# DDR-LPDDR4.net
KiCad netlist of a schematic drawn in Altium Designer
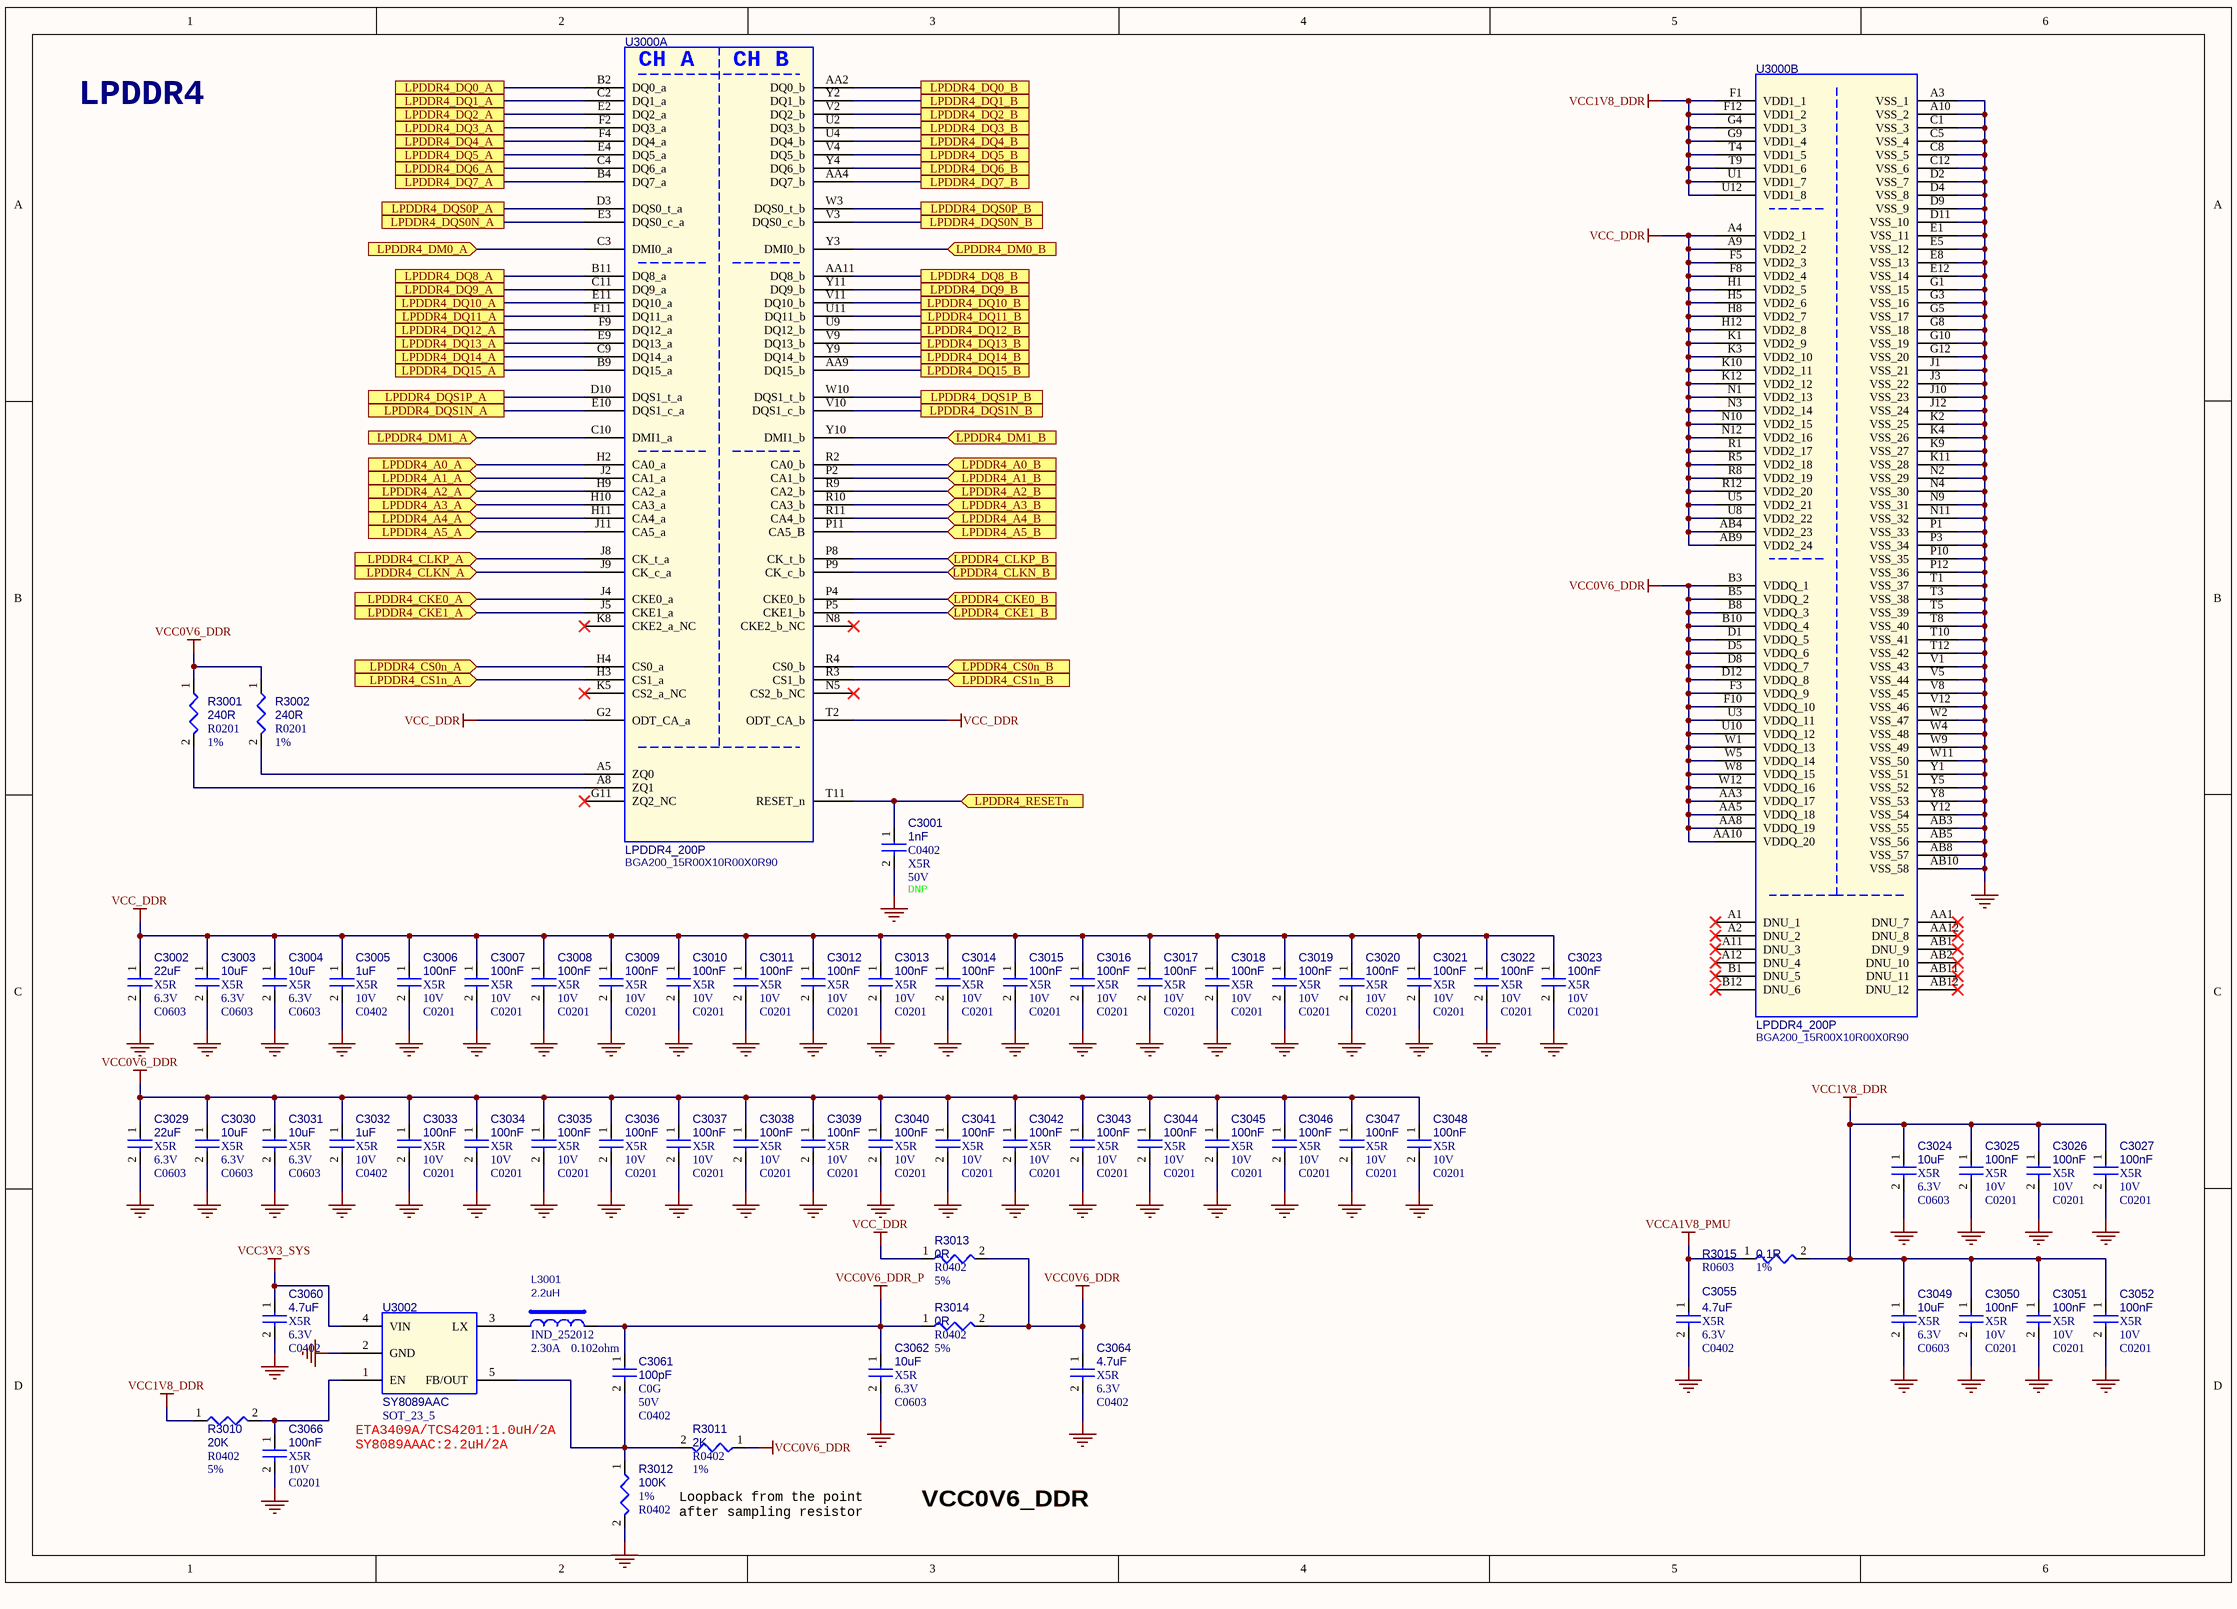
[diagram p0: DDR-LPDDR4.SchDoc]

(export (version "E")
  (design (tool "Eeschema 10.0.6"))
  (components
    (comp (ref "C3001")
      (value "1nF")
      (footprint "C0402")
      (description "cap,1.00nF,+/-10%,50V,X5R,C0402")
      (fields
        (field (name "DIELECTRIC") "X5R")
        (field (name "PCB FOOTPRINT") "C0402")
        (field (name "VOLTAGE") "50V")
        (field (name "OPTION") "DNP")
        (field (name "TOLERANCE") "10%")
        (field (name "MANUFACTURER") "TDK")
        (field (name "CREATED BY") "JJJ")
      )
      (libsource (lib "RK3562_REF") (part "CAP NP"))
    )
    (comp (ref "C3002")
      (value "22uF")
      (footprint "C0603")
      (description "cap,22.00uF,+/-20%,6.3V,X5R,C0603")
      (fields
        (field (name "DIELECTRIC") "X5R")
        (field (name "PCB FOOTPRINT") "C0603")
        (field (name "VOLTAGE") "6.3V")
        (field (name "MANUFACTURER") "TDK")
        (field (name "TOLERANCE") "20%")
        (field (name "CREATED BY") "JJJ")
      )
      (libsource (lib "RK3562_REF") (part "CAP NP"))
    )
    (comp (ref "C3003")
      (value "10uF")
      (footprint "C0603")
      (description "cap,10.00uF,+/-10%,6.3V,X5R,C0603")
      (fields
        (field (name "DIELECTRIC") "X5R")
        (field (name "PCB FOOTPRINT") "C0603")
        (field (name "VOLTAGE") "6.3V")
        (field (name "MANUFACTURER") "TDK")
        (field (name "TOLERANCE") "10%")
        (field (name "CREATED BY") "JJJ")
      )
      (libsource (lib "RK3562_REF") (part "CAP NP"))
    )
    (comp (ref "C3004")
      (value "10uF")
      (footprint "C0603")
      (description "cap,10.00uF,+/-10%,6.3V,X5R,C0603")
      (fields
        (field (name "DIELECTRIC") "X5R")
        (field (name "PCB FOOTPRINT") "C0603")
        (field (name "VOLTAGE") "6.3V")
        (field (name "TOLERANCE") "10%")
        (field (name "MANUFACTURER") "TDK")
        (field (name "CREATED BY") "JJJ")
      )
      (libsource (lib "RK3562_REF") (part "CAP NP"))
    )
    (comp (ref "C3005")
      (value "1uF")
      (footprint "C0402")
      (description "cap,1.00uF,+/-10%,10V,X5R,C0402")
      (fields
        (field (name "DIELECTRIC") "X5R")
        (field (name "PCB FOOTPRINT") "C0402")
        (field (name "VOLTAGE") "10V")
        (field (name "MANUFACTURER") "TDK")
        (field (name "TOLERANCE") "10%")
        (field (name "CREATED BY") "JJJ")
      )
      (libsource (lib "RK3562_REF") (part "CAP NP"))
    )
    (comp (ref "C3006")
      (value "100nF")
      (footprint "C0201")
      (description "cap,100.00nF,+/-10%,10V,X5R,C0201")
      (fields
        (field (name "DIELECTRIC") "X5R")
        (field (name "PCB FOOTPRINT") "C0201")
        (field (name "VOLTAGE") "10V")
        (field (name "MANUFACTURER") "TDK")
        (field (name "TOLERANCE") "10%")
        (field (name "CREATED BY") "JJJ")
      )
      (libsource (lib "RK3562_REF") (part "CAP NP"))
    )
    (comp (ref "C3007")
      (value "100nF")
      (footprint "C0201")
      (description "cap,100.00nF,+/-10%,10V,X5R,C0201")
      (fields
        (field (name "DIELECTRIC") "X5R")
        (field (name "PCB FOOTPRINT") "C0201")
        (field (name "VOLTAGE") "10V")
        (field (name "MANUFACTURER") "TDK")
        (field (name "TOLERANCE") "10%")
        (field (name "CREATED BY") "JJJ")
      )
      (libsource (lib "RK3562_REF") (part "CAP NP"))
    )
    (comp (ref "C3008")
      (value "100nF")
      (footprint "C0201")
      (description "cap,100.00nF,+/-10%,10V,X5R,C0201")
      (fields
        (field (name "DIELECTRIC") "X5R")
        (field (name "PCB FOOTPRINT") "C0201")
        (field (name "VOLTAGE") "10V")
        (field (name "MANUFACTURER") "TDK")
        (field (name "TOLERANCE") "10%")
        (field (name "CREATED BY") "JJJ")
      )
      (libsource (lib "RK3562_REF") (part "CAP NP"))
    )
    (comp (ref "C3009")
      (value "100nF")
      (footprint "C0201")
      (description "cap,100.00nF,+/-10%,10V,X5R,C0201")
      (fields
        (field (name "DIELECTRIC") "X5R")
        (field (name "PCB FOOTPRINT") "C0201")
        (field (name "VOLTAGE") "10V")
        (field (name "MANUFACTURER") "TDK")
        (field (name "TOLERANCE") "10%")
        (field (name "CREATED BY") "JJJ")
      )
      (libsource (lib "RK3562_REF") (part "CAP NP"))
    )
    (comp (ref "C3010")
      (value "100nF")
      (footprint "C0201")
      (description "cap,100.00nF,+/-10%,10V,X5R,C0201")
      (fields
        (field (name "DIELECTRIC") "X5R")
        (field (name "PCB FOOTPRINT") "C0201")
        (field (name "VOLTAGE") "10V")
        (field (name "MANUFACTURER") "TDK")
        (field (name "TOLERANCE") "10%")
        (field (name "CREATED BY") "JJJ")
      )
      (libsource (lib "RK3562_REF") (part "CAP NP"))
    )
    (comp (ref "C3011")
      (value "100nF")
      (footprint "C0201")
      (description "cap,100.00nF,+/-10%,10V,X5R,C0201")
      (fields
        (field (name "DIELECTRIC") "X5R")
        (field (name "PCB FOOTPRINT") "C0201")
        (field (name "VOLTAGE") "10V")
        (field (name "MANUFACTURER") "TDK")
        (field (name "TOLERANCE") "10%")
        (field (name "CREATED BY") "JJJ")
      )
      (libsource (lib "RK3562_REF") (part "CAP NP"))
    )
    (comp (ref "C3012")
      (value "100nF")
      (footprint "C0201")
      (description "cap,100.00nF,+/-10%,10V,X5R,C0201")
      (fields
        (field (name "DIELECTRIC") "X5R")
        (field (name "PCB FOOTPRINT") "C0201")
        (field (name "VOLTAGE") "10V")
        (field (name "TOLERANCE") "10%")
        (field (name "MANUFACTURER") "TDK")
        (field (name "CREATED BY") "JJJ")
      )
      (libsource (lib "RK3562_REF") (part "CAP NP"))
    )
    (comp (ref "C3013")
      (value "100nF")
      (footprint "C0201")
      (description "cap,100.00nF,+/-10%,10V,X5R,C0201")
      (fields
        (field (name "DIELECTRIC") "X5R")
        (field (name "PCB FOOTPRINT") "C0201")
        (field (name "VOLTAGE") "10V")
        (field (name "TOLERANCE") "10%")
        (field (name "MANUFACTURER") "TDK")
        (field (name "CREATED BY") "JJJ")
      )
      (libsource (lib "RK3562_REF") (part "CAP NP"))
    )
    (comp (ref "C3014")
      (value "100nF")
      (footprint "C0201")
      (description "cap,100.00nF,+/-10%,10V,X5R,C0201")
      (fields
        (field (name "DIELECTRIC") "X5R")
        (field (name "PCB FOOTPRINT") "C0201")
        (field (name "VOLTAGE") "10V")
        (field (name "TOLERANCE") "10%")
        (field (name "MANUFACTURER") "TDK")
        (field (name "CREATED BY") "JJJ")
      )
      (libsource (lib "RK3562_REF") (part "CAP NP"))
    )
    (comp (ref "C3015")
      (value "100nF")
      (footprint "C0201")
      (description "cap,100.00nF,+/-10%,10V,X5R,C0201")
      (fields
        (field (name "DIELECTRIC") "X5R")
        (field (name "PCB FOOTPRINT") "C0201")
        (field (name "VOLTAGE") "10V")
        (field (name "TOLERANCE") "10%")
        (field (name "MANUFACTURER") "TDK")
        (field (name "CREATED BY") "JJJ")
      )
      (libsource (lib "RK3562_REF") (part "CAP NP"))
    )
    (comp (ref "C3016")
      (value "100nF")
      (footprint "C0201")
      (description "cap,100.00nF,+/-10%,10V,X5R,C0201")
      (fields
        (field (name "DIELECTRIC") "X5R")
        (field (name "PCB FOOTPRINT") "C0201")
        (field (name "VOLTAGE") "10V")
        (field (name "TOLERANCE") "10%")
        (field (name "MANUFACTURER") "TDK")
        (field (name "CREATED BY") "JJJ")
      )
      (libsource (lib "RK3562_REF") (part "CAP NP"))
    )
    (comp (ref "C3017")
      (value "100nF")
      (footprint "C0201")
      (description "cap,100.00nF,+/-10%,10V,X5R,C0201")
      (fields
        (field (name "DIELECTRIC") "X5R")
        (field (name "PCB FOOTPRINT") "C0201")
        (field (name "VOLTAGE") "10V")
        (field (name "MANUFACTURER") "TDK")
        (field (name "TOLERANCE") "10%")
        (field (name "CREATED BY") "JJJ")
      )
      (libsource (lib "RK3562_REF") (part "CAP NP"))
    )
    (comp (ref "C3018")
      (value "100nF")
      (footprint "C0201")
      (description "cap,100.00nF,+/-10%,10V,X5R,C0201")
      (fields
        (field (name "DIELECTRIC") "X5R")
        (field (name "PCB FOOTPRINT") "C0201")
        (field (name "VOLTAGE") "10V")
        (field (name "MANUFACTURER") "TDK")
        (field (name "TOLERANCE") "10%")
        (field (name "CREATED BY") "JJJ")
      )
      (libsource (lib "RK3562_REF") (part "CAP NP"))
    )
    (comp (ref "C3019")
      (value "100nF")
      (footprint "C0201")
      (description "cap,100.00nF,+/-10%,10V,X5R,C0201")
      (fields
        (field (name "DIELECTRIC") "X5R")
        (field (name "PCB FOOTPRINT") "C0201")
        (field (name "VOLTAGE") "10V")
        (field (name "TOLERANCE") "10%")
        (field (name "MANUFACTURER") "TDK")
        (field (name "CREATED BY") "JJJ")
      )
      (libsource (lib "RK3562_REF") (part "CAP NP"))
    )
    (comp (ref "C3020")
      (value "100nF")
      (footprint "C0201")
      (description "cap,100.00nF,+/-10%,10V,X5R,C0201")
      (fields
        (field (name "DIELECTRIC") "X5R")
        (field (name "PCB FOOTPRINT") "C0201")
        (field (name "VOLTAGE") "10V")
        (field (name "TOLERANCE") "10%")
        (field (name "MANUFACTURER") "TDK")
        (field (name "CREATED BY") "JJJ")
      )
      (libsource (lib "RK3562_REF") (part "CAP NP"))
    )
    (comp (ref "C3021")
      (value "100nF")
      (footprint "C0201")
      (description "cap,100.00nF,+/-10%,10V,X5R,C0201")
      (fields
        (field (name "DIELECTRIC") "X5R")
        (field (name "PCB FOOTPRINT") "C0201")
        (field (name "VOLTAGE") "10V")
        (field (name "TOLERANCE") "10%")
        (field (name "MANUFACTURER") "TDK")
        (field (name "CREATED BY") "JJJ")
      )
      (libsource (lib "RK3562_REF") (part "CAP NP"))
    )
    (comp (ref "C3022")
      (value "100nF")
      (footprint "C0201")
      (description "cap,100.00nF,+/-10%,10V,X5R,C0201")
      (fields
        (field (name "DIELECTRIC") "X5R")
        (field (name "PCB FOOTPRINT") "C0201")
        (field (name "VOLTAGE") "10V")
        (field (name "MANUFACTURER") "TDK")
        (field (name "TOLERANCE") "10%")
        (field (name "CREATED BY") "JJJ")
      )
      (libsource (lib "RK3562_REF") (part "CAP NP"))
    )
    (comp (ref "C3023")
      (value "100nF")
      (footprint "C0201")
      (description "cap,100.00nF,+/-10%,10V,X5R,C0201")
      (fields
        (field (name "DIELECTRIC") "X5R")
        (field (name "PCB FOOTPRINT") "C0201")
        (field (name "VOLTAGE") "10V")
        (field (name "MANUFACTURER") "TDK")
        (field (name "TOLERANCE") "10%")
        (field (name "CREATED BY") "JJJ")
      )
      (libsource (lib "RK3562_REF") (part "CAP NP"))
    )
    (comp (ref "C3024")
      (value "10uF")
      (footprint "C0603")
      (description "cap,10.00uF,+/-10%,6.3V,X5R,C0603")
      (fields
        (field (name "DIELECTRIC") "X5R")
        (field (name "PCB FOOTPRINT") "C0603")
        (field (name "VOLTAGE") "6.3V")
        (field (name "TOLERANCE") "10%")
        (field (name "MANUFACTURER") "TDK")
        (field (name "CREATED BY") "JJJ")
      )
      (libsource (lib "RK3562_REF") (part "CAP NP"))
    )
    (comp (ref "C3025")
      (value "100nF")
      (footprint "C0201")
      (description "cap,100.00nF,+/-10%,10V,X5R,C0201")
      (fields
        (field (name "DIELECTRIC") "X5R")
        (field (name "PCB FOOTPRINT") "C0201")
        (field (name "VOLTAGE") "10V")
        (field (name "TOLERANCE") "10%")
        (field (name "MANUFACTURER") "TDK")
        (field (name "CREATED BY") "JJJ")
      )
      (libsource (lib "RK3562_REF") (part "CAP NP"))
    )
    (comp (ref "C3026")
      (value "100nF")
      (footprint "C0201")
      (description "cap,100.00nF,+/-10%,10V,X5R,C0201")
      (fields
        (field (name "DIELECTRIC") "X5R")
        (field (name "PCB FOOTPRINT") "C0201")
        (field (name "VOLTAGE") "10V")
        (field (name "TOLERANCE") "10%")
        (field (name "MANUFACTURER") "TDK")
        (field (name "CREATED BY") "JJJ")
      )
      (libsource (lib "RK3562_REF") (part "CAP NP"))
    )
    (comp (ref "C3027")
      (value "100nF")
      (footprint "C0201")
      (description "cap,100.00nF,+/-10%,10V,X5R,C0201")
      (fields
        (field (name "DIELECTRIC") "X5R")
        (field (name "PCB FOOTPRINT") "C0201")
        (field (name "VOLTAGE") "10V")
        (field (name "TOLERANCE") "10%")
        (field (name "MANUFACTURER") "TDK")
        (field (name "CREATED BY") "JJJ")
      )
      (libsource (lib "RK3562_REF") (part "CAP NP"))
    )
    (comp (ref "C3029")
      (value "22uF")
      (footprint "C0603")
      (description "cap,22.00uF,+/-20%,6.3V,X5R,C0603")
      (fields
        (field (name "DIELECTRIC") "X5R")
        (field (name "PCB FOOTPRINT") "C0603")
        (field (name "VOLTAGE") "6.3V")
        (field (name "TOLERANCE") "20%")
        (field (name "MANUFACTURER") "TDK")
        (field (name "CREATED BY") "JJJ")
      )
      (libsource (lib "RK3562_REF") (part "CAP NP"))
    )
    (comp (ref "C3030")
      (value "10uF")
      (footprint "C0603")
      (description "cap,10.00uF,+/-10%,6.3V,X5R,C0603")
      (fields
        (field (name "DIELECTRIC") "X5R")
        (field (name "PCB FOOTPRINT") "C0603")
        (field (name "VOLTAGE") "6.3V")
        (field (name "MANUFACTURER") "TDK")
        (field (name "TOLERANCE") "10%")
        (field (name "CREATED BY") "JJJ")
      )
      (libsource (lib "RK3562_REF") (part "CAP NP"))
    )
    (comp (ref "C3031")
      (value "10uF")
      (footprint "C0603")
      (description "cap,10.00uF,+/-10%,6.3V,X5R,C0603")
      (fields
        (field (name "DIELECTRIC") "X5R")
        (field (name "PCB FOOTPRINT") "C0603")
        (field (name "VOLTAGE") "6.3V")
        (field (name "TOLERANCE") "10%")
        (field (name "MANUFACTURER") "TDK")
        (field (name "CREATED BY") "JJJ")
      )
      (libsource (lib "RK3562_REF") (part "CAP NP"))
    )
    (comp (ref "C3032")
      (value "1uF")
      (footprint "C0402")
      (description "cap,1.00uF,+/-10%,10V,X5R,C0402")
      (fields
        (field (name "DIELECTRIC") "X5R")
        (field (name "PCB FOOTPRINT") "C0402")
        (field (name "VOLTAGE") "10V")
        (field (name "TOLERANCE") "10%")
        (field (name "MANUFACTURER") "TDK")
        (field (name "CREATED BY") "JJJ")
      )
      (libsource (lib "RK3562_REF") (part "CAP NP"))
    )
    (comp (ref "C3033")
      (value "100nF")
      (footprint "C0201")
      (description "cap,100.00nF,+/-10%,10V,X5R,C0201")
      (fields
        (field (name "DIELECTRIC") "X5R")
        (field (name "PCB FOOTPRINT") "C0201")
        (field (name "VOLTAGE") "10V")
        (field (name "TOLERANCE") "10%")
        (field (name "MANUFACTURER") "TDK")
        (field (name "CREATED BY") "JJJ")
      )
      (libsource (lib "RK3562_REF") (part "CAP NP"))
    )
    (comp (ref "C3034")
      (value "100nF")
      (footprint "C0201")
      (description "cap,100.00nF,+/-10%,10V,X5R,C0201")
      (fields
        (field (name "DIELECTRIC") "X5R")
        (field (name "PCB FOOTPRINT") "C0201")
        (field (name "VOLTAGE") "10V")
        (field (name "MANUFACTURER") "TDK")
        (field (name "TOLERANCE") "10%")
        (field (name "CREATED BY") "JJJ")
      )
      (libsource (lib "RK3562_REF") (part "CAP NP"))
    )
    (comp (ref "C3035")
      (value "100nF")
      (footprint "C0201")
      (description "cap,100.00nF,+/-10%,10V,X5R,C0201")
      (fields
        (field (name "DIELECTRIC") "X5R")
        (field (name "PCB FOOTPRINT") "C0201")
        (field (name "VOLTAGE") "10V")
        (field (name "TOLERANCE") "10%")
        (field (name "MANUFACTURER") "TDK")
        (field (name "CREATED BY") "JJJ")
      )
      (libsource (lib "RK3562_REF") (part "CAP NP"))
    )
    (comp (ref "C3036")
      (value "100nF")
      (footprint "C0201")
      (description "cap,100.00nF,+/-10%,10V,X5R,C0201")
      (fields
        (field (name "DIELECTRIC") "X5R")
        (field (name "PCB FOOTPRINT") "C0201")
        (field (name "VOLTAGE") "10V")
        (field (name "TOLERANCE") "10%")
        (field (name "MANUFACTURER") "TDK")
        (field (name "CREATED BY") "JJJ")
      )
      (libsource (lib "RK3562_REF") (part "CAP NP"))
    )
    (comp (ref "C3037")
      (value "100nF")
      (footprint "C0201")
      (description "cap,100.00nF,+/-10%,10V,X5R,C0201")
      (fields
        (field (name "DIELECTRIC") "X5R")
        (field (name "PCB FOOTPRINT") "C0201")
        (field (name "VOLTAGE") "10V")
        (field (name "TOLERANCE") "10%")
        (field (name "MANUFACTURER") "TDK")
        (field (name "CREATED BY") "JJJ")
      )
      (libsource (lib "RK3562_REF") (part "CAP NP"))
    )
    (comp (ref "C3038")
      (value "100nF")
      (footprint "C0201")
      (description "cap,100.00nF,+/-10%,10V,X5R,C0201")
      (fields
        (field (name "DIELECTRIC") "X5R")
        (field (name "PCB FOOTPRINT") "C0201")
        (field (name "VOLTAGE") "10V")
        (field (name "TOLERANCE") "10%")
        (field (name "MANUFACTURER") "TDK")
        (field (name "CREATED BY") "JJJ")
      )
      (libsource (lib "RK3562_REF") (part "CAP NP"))
    )
    (comp (ref "C3039")
      (value "100nF")
      (footprint "C0201")
      (description "cap,100.00nF,+/-10%,10V,X5R,C0201")
      (fields
        (field (name "DIELECTRIC") "X5R")
        (field (name "PCB FOOTPRINT") "C0201")
        (field (name "VOLTAGE") "10V")
        (field (name "MANUFACTURER") "TDK")
        (field (name "TOLERANCE") "10%")
        (field (name "CREATED BY") "JJJ")
      )
      (libsource (lib "RK3562_REF") (part "CAP NP"))
    )
    (comp (ref "C3040")
      (value "100nF")
      (footprint "C0201")
      (description "cap,100.00nF,+/-10%,10V,X5R,C0201")
      (fields
        (field (name "DIELECTRIC") "X5R")
        (field (name "PCB FOOTPRINT") "C0201")
        (field (name "VOLTAGE") "10V")
        (field (name "MANUFACTURER") "TDK")
        (field (name "TOLERANCE") "10%")
        (field (name "CREATED BY") "JJJ")
      )
      (libsource (lib "RK3562_REF") (part "CAP NP"))
    )
    (comp (ref "C3041")
      (value "100nF")
      (footprint "C0201")
      (description "cap,100.00nF,+/-10%,10V,X5R,C0201")
      (fields
        (field (name "DIELECTRIC") "X5R")
        (field (name "PCB FOOTPRINT") "C0201")
        (field (name "VOLTAGE") "10V")
        (field (name "MANUFACTURER") "TDK")
        (field (name "TOLERANCE") "10%")
        (field (name "CREATED BY") "JJJ")
      )
      (libsource (lib "RK3562_REF") (part "CAP NP"))
    )
    (comp (ref "C3042")
      (value "100nF")
      (footprint "C0201")
      (description "cap,100.00nF,+/-10%,10V,X5R,C0201")
      (fields
        (field (name "DIELECTRIC") "X5R")
        (field (name "PCB FOOTPRINT") "C0201")
        (field (name "VOLTAGE") "10V")
        (field (name "MANUFACTURER") "TDK")
        (field (name "TOLERANCE") "10%")
        (field (name "CREATED BY") "JJJ")
      )
      (libsource (lib "RK3562_REF") (part "CAP NP"))
    )
    (comp (ref "C3043")
      (value "100nF")
      (footprint "C0201")
      (description "cap,100.00nF,+/-10%,10V,X5R,C0201")
      (fields
        (field (name "DIELECTRIC") "X5R")
        (field (name "PCB FOOTPRINT") "C0201")
        (field (name "VOLTAGE") "10V")
        (field (name "TOLERANCE") "10%")
        (field (name "MANUFACTURER") "TDK")
        (field (name "CREATED BY") "JJJ")
      )
      (libsource (lib "RK3562_REF") (part "CAP NP"))
    )
    (comp (ref "C3044")
      (value "100nF")
      (footprint "C0201")
      (description "cap,100.00nF,+/-10%,10V,X5R,C0201")
      (fields
        (field (name "DIELECTRIC") "X5R")
        (field (name "PCB FOOTPRINT") "C0201")
        (field (name "VOLTAGE") "10V")
        (field (name "TOLERANCE") "10%")
        (field (name "MANUFACTURER") "TDK")
        (field (name "CREATED BY") "JJJ")
      )
      (libsource (lib "RK3562_REF") (part "CAP NP"))
    )
    (comp (ref "C3045")
      (value "100nF")
      (footprint "C0201")
      (description "cap,100.00nF,+/-10%,10V,X5R,C0201")
      (fields
        (field (name "DIELECTRIC") "X5R")
        (field (name "PCB FOOTPRINT") "C0201")
        (field (name "VOLTAGE") "10V")
        (field (name "TOLERANCE") "10%")
        (field (name "MANUFACTURER") "TDK")
        (field (name "CREATED BY") "JJJ")
      )
      (libsource (lib "RK3562_REF") (part "CAP NP"))
    )
    (comp (ref "C3046")
      (value "100nF")
      (footprint "C0201")
      (description "cap,100.00nF,+/-10%,10V,X5R,C0201")
      (fields
        (field (name "DIELECTRIC") "X5R")
        (field (name "PCB FOOTPRINT") "C0201")
        (field (name "VOLTAGE") "10V")
        (field (name "MANUFACTURER") "TDK")
        (field (name "TOLERANCE") "10%")
        (field (name "CREATED BY") "JJJ")
      )
      (libsource (lib "RK3562_REF") (part "CAP NP"))
    )
    (comp (ref "C3047")
      (value "100nF")
      (footprint "C0201")
      (description "cap,100.00nF,+/-10%,10V,X5R,C0201")
      (fields
        (field (name "DIELECTRIC") "X5R")
        (field (name "PCB FOOTPRINT") "C0201")
        (field (name "VOLTAGE") "10V")
        (field (name "MANUFACTURER") "TDK")
        (field (name "TOLERANCE") "10%")
        (field (name "CREATED BY") "JJJ")
      )
      (libsource (lib "RK3562_REF") (part "CAP NP"))
    )
    (comp (ref "C3048")
      (value "100nF")
      (footprint "C0201")
      (description "cap,100.00nF,+/-10%,10V,X5R,C0201")
      (fields
        (field (name "DIELECTRIC") "X5R")
        (field (name "PCB FOOTPRINT") "C0201")
        (field (name "VOLTAGE") "10V")
        (field (name "TOLERANCE") "10%")
        (field (name "MANUFACTURER") "TDK")
        (field (name "CREATED BY") "JJJ")
      )
      (libsource (lib "RK3562_REF") (part "CAP NP"))
    )
    (comp (ref "C3049")
      (value "10uF")
      (footprint "C0603")
      (description "cap,10.00uF,+/-10%,6.3V,X5R,C0603")
      (fields
        (field (name "DIELECTRIC") "X5R")
        (field (name "PCB FOOTPRINT") "C0603")
        (field (name "VOLTAGE") "6.3V")
        (field (name "TOLERANCE") "10%")
        (field (name "MANUFACTURER") "TDK")
        (field (name "CREATED BY") "JJJ")
      )
      (libsource (lib "RK3562_REF") (part "CAP NP"))
    )
    (comp (ref "C3050")
      (value "100nF")
      (footprint "C0201")
      (description "cap,100.00nF,+/-10%,10V,X5R,C0201")
      (fields
        (field (name "DIELECTRIC") "X5R")
        (field (name "PCB FOOTPRINT") "C0201")
        (field (name "VOLTAGE") "10V")
        (field (name "MANUFACTURER") "TDK")
        (field (name "TOLERANCE") "10%")
        (field (name "CREATED BY") "JJJ")
      )
      (libsource (lib "RK3562_REF") (part "CAP NP"))
    )
    (comp (ref "C3051")
      (value "100nF")
      (footprint "C0201")
      (description "cap,100.00nF,+/-10%,10V,X5R,C0201")
      (fields
        (field (name "DIELECTRIC") "X5R")
        (field (name "PCB FOOTPRINT") "C0201")
        (field (name "VOLTAGE") "10V")
        (field (name "MANUFACTURER") "TDK")
        (field (name "TOLERANCE") "10%")
        (field (name "CREATED BY") "JJJ")
      )
      (libsource (lib "RK3562_REF") (part "CAP NP"))
    )
    (comp (ref "C3052")
      (value "100nF")
      (footprint "C0201")
      (description "cap,100.00nF,+/-10%,10V,X5R,C0201")
      (fields
        (field (name "DIELECTRIC") "X5R")
        (field (name "PCB FOOTPRINT") "C0201")
        (field (name "VOLTAGE") "10V")
        (field (name "MANUFACTURER") "TDK")
        (field (name "TOLERANCE") "10%")
        (field (name "CREATED BY") "JJJ")
      )
      (libsource (lib "RK3562_REF") (part "CAP NP"))
    )
    (comp (ref "C3055")
      (value "4.7uF")
      (footprint "C0402")
      (description "cap,4.70uF,+/-10%,6.3V,X5R,C0402")
      (fields
        (field (name "DIELECTRIC") "X5R")
        (field (name "PCB FOOTPRINT") "C0402")
        (field (name "VOLTAGE") "6.3V")
        (field (name "TOLERANCE") "10%")
        (field (name "MANUFACTURER") "TDK")
        (field (name "CREATED BY") "JJJ")
      )
      (libsource (lib "RK3562_REF") (part "CAP NP"))
    )
    (comp (ref "C3060")
      (value "4.7uF")
      (footprint "C0402")
      (description "cap,4.70uF,+/-10%,6.3V,X5R,C0402")
      (fields
        (field (name "DIELECTRIC") "X5R")
        (field (name "PCB FOOTPRINT") "C0402")
        (field (name "VOLTAGE") "6.3V")
        (field (name "MANUFACTURER") "TDK")
        (field (name "TOLERANCE") "10%")
        (field (name "CREATED BY") "JJJ")
      )
      (libsource (lib "RK3562_REF") (part "CAP NP"))
    )
    (comp (ref "C3061")
      (value "100pF")
      (footprint "C0402")
      (description "cap,100.00pF,+/-10%,50V,C0G,C0402")
      (fields
        (field (name "DIELECTRIC") "C0G")
        (field (name "PCB FOOTPRINT") "C0402")
        (field (name "VOLTAGE") "50V")
        (field (name "MANUFACTURER") "TDK")
        (field (name "TOLERANCE") "10%")
        (field (name "CREATED BY") "JJJ")
      )
      (libsource (lib "RK3562_REF") (part "CAP NP"))
    )
    (comp (ref "C3062")
      (value "10uF")
      (footprint "C0603")
      (description "cap,10.00uF,+/-10%,6.3V,X5R,C0603")
      (fields
        (field (name "DIELECTRIC") "X5R")
        (field (name "PCB FOOTPRINT") "C0603")
        (field (name "VOLTAGE") "6.3V")
        (field (name "TOLERANCE") "10%")
        (field (name "MANUFACTURER") "TDK")
        (field (name "CREATED BY") "JJJ")
      )
      (libsource (lib "RK3562_REF") (part "CAP NP"))
    )
    (comp (ref "C3064")
      (value "4.7uF")
      (footprint "C0402")
      (description "cap,4.70uF,+/-10%,6.3V,X5R,C0402")
      (fields
        (field (name "DIELECTRIC") "X5R")
        (field (name "PCB FOOTPRINT") "C0402")
        (field (name "VOLTAGE") "6.3V")
        (field (name "MANUFACTURER") "TDK")
        (field (name "TOLERANCE") "10%")
        (field (name "CREATED BY") "JJJ")
      )
      (libsource (lib "RK3562_REF") (part "CAP NP"))
    )
    (comp (ref "C3066")
      (value "100nF")
      (footprint "C0201")
      (description "cap,100.00nF,+/-10%,10V,X5R,C0201")
      (fields
        (field (name "DIELECTRIC") "X5R")
        (field (name "PCB FOOTPRINT") "C0201")
        (field (name "VOLTAGE") "10V")
        (field (name "TOLERANCE") "10%")
        (field (name "MANUFACTURER") "TDK")
        (field (name "CREATED BY") "JJJ")
      )
      (libsource (lib "RK3562_REF") (part "CAP NP"))
    )
    (comp (ref "L3001")
      (value "2.2uH")
      (footprint "IND_252012")
      (description "Power Inductor,2.2uH,20%,IND_252012")
      (fields
        (field (name "PCB FOOTPRINT") "IND_252012")
        (field (name "ISAT") "2.30A")
        (field (name "DC RESISTOR") "0.102ohm")
        (field (name "MANUFACTURER") "TDK")
        (field (name "TOLERANCE") "20%")
        (field (name "CREATED BY") "JJJ")
      )
      (libsource (lib "RK3562_REF") (part "INDUCTORS OF FERRITE"))
    )
    (comp (ref "R3001")
      (value "240R")
      (footprint "R0201")
      (description "通用厚膜电阻,240R,+/-1%,R0201,1/20W.")
      (fields
        (field (name "TOLERANCE") "1%")
        (field (name "PCB FOOTPRINT") "R0201")
        (field (name "MANUFACTURER") "YAGEO")
        (field (name "CREATED BY") "YTL")
      )
      (libsource (lib "RK3562_REF") (part "RESISTOR"))
    )
    (comp (ref "R3002")
      (value "240R")
      (footprint "R0201")
      (description "通用厚膜电阻,240R,+/-1%,R0201,1/20W.")
      (fields
        (field (name "TOLERANCE") "1%")
        (field (name "PCB FOOTPRINT") "R0201")
        (field (name "MANUFACTURER") "YAGEO")
        (field (name "CREATED BY") "YTL")
      )
      (libsource (lib "RK3562_REF") (part "RESISTOR"))
    )
    (comp (ref "R3010")
      (value "20K")
      (footprint "R0402")
      (description "通用厚膜电阻,20K,+/-5%,R0402,1/16W.")
      (fields
        (field (name "TOLERANCE") "5%")
        (field (name "PCB FOOTPRINT") "R0402")
        (field (name "MANUFACTURER") "YAGEO")
        (field (name "CREATED BY") "YTL")
      )
      (libsource (lib "RK3562_REF") (part "RESISTOR"))
    )
    (comp (ref "R3011")
      (value "2K")
      (footprint "R0402")
      (description "通用厚膜电阻,2K,+/-1%,R0402,1/16W.")
      (fields
        (field (name "TOLERANCE") "1%")
        (field (name "PCB FOOTPRINT") "R0402")
        (field (name "MANUFACTURER") "YAGEO")
        (field (name "CREATED BY") "YTL")
      )
      (libsource (lib "RK3562_REF") (part "RESISTOR"))
    )
    (comp (ref "R3012")
      (value "100K")
      (footprint "R0402")
      (description "通用厚膜电阻,100K,+/-1%,R0402,1/16W.")
      (fields
        (field (name "TOLERANCE") "1%")
        (field (name "PCB FOOTPRINT") "R0402")
        (field (name "MANUFACTURER") "YAGEO")
        (field (name "CREATED BY") "YTL")
      )
      (libsource (lib "RK3562_REF") (part "RESISTOR"))
    )
    (comp (ref "R3013")
      (value "0R")
      (footprint "R0402")
      (description "通用厚膜电阻,0R,+/-5%,R0402,1/16W.")
      (fields
        (field (name "TOLERANCE") "5%")
        (field (name "PCB FOOTPRINT") "R0402")
        (field (name "MANUFACTURER") "YAGEO")
        (field (name "CREATED BY") "YTL")
      )
      (libsource (lib "RK3562_REF") (part "RESISTOR"))
    )
    (comp (ref "R3014")
      (value "0R")
      (footprint "R0402")
      (description "通用厚膜电阻,0R,+/-5%,R0402,1/16W.")
      (fields
        (field (name "TOLERANCE") "5%")
        (field (name "PCB FOOTPRINT") "R0402")
        (field (name "MANUFACTURER") "YAGEO")
        (field (name "CREATED BY") "YTL")
      )
      (libsource (lib "RK3562_REF") (part "RESISTOR"))
    )
    (comp (ref "R3015")
      (value "0.1R")
      (footprint "R0603")
      (description "厚膜低阻值电阻,0R1,+/-1%,R0603,1/10W.")
      (fields
        (field (name "TOLERANCE") "1%")
        (field (name "PCB FOOTPRINT") "R0603")
        (field (name "MANUFACTURER") "YAGEO")
        (field (name "CREATED BY") "YTL")
      )
      (libsource (lib "RK3562_REF") (part "RESISTOR"))
    )
    (comp (ref "U3000")
      (value "LPDDR4_200P")
      (footprint "BGA200_15R00X10R00X0R90")
      (fields (field (name "PCB FOOTPRINT") "BGA200_15R00X10R00X0R90"))
      (libsource (lib "RK3562_REF") (part "LPDDR4_200P_0"))
    )
    (comp (ref "U3002")
      (value "SY8089AAC")
      (footprint "SOT_23_5")
      (fields
        (field (name "PCB FOOTPRINT") "SOT_23_5")
        (field (name "MANUFACTURER") "Silergy（矽力杰）")
        (field (name "CREATED BY") "JJJ")
      )
      (libsource (lib "RK3562_REF") (part "DCDC_SY8088"))
    )
  )
  (nets
    (net (code "1") (name "/LPDDR4_A0_A") (class "Default")
      (node (ref "U3000") (pin "H2") (pinfunction "CA0_a_H2") (pintype "passive"))
    )
    (net (code "2") (name "/LPDDR4_A0_B") (class "Default")
      (node (ref "U3000") (pin "R2") (pinfunction "CA0_b_R2") (pintype "passive"))
    )
    (net (code "3") (name "/LPDDR4_A1_A") (class "Default")
      (node (ref "U3000") (pin "J2") (pinfunction "CA1_a_J2") (pintype "passive"))
    )
    (net (code "4") (name "/LPDDR4_A1_B") (class "Default")
      (node (ref "U3000") (pin "P2") (pinfunction "CA1_b_P2") (pintype "passive"))
    )
    (net (code "5") (name "/LPDDR4_A2_A") (class "Default")
      (node (ref "U3000") (pin "H9") (pinfunction "CA2_a_H9") (pintype "passive"))
    )
    (net (code "6") (name "/LPDDR4_A2_B") (class "Default")
      (node (ref "U3000") (pin "R9") (pinfunction "CA2_b_R9") (pintype "passive"))
    )
    (net (code "7") (name "/LPDDR4_A3_A") (class "Default")
      (node (ref "U3000") (pin "H10") (pinfunction "CA3_a_H10") (pintype "passive"))
    )
    (net (code "8") (name "/LPDDR4_A3_B") (class "Default")
      (node (ref "U3000") (pin "R10") (pinfunction "CA3_b_R10") (pintype "passive"))
    )
    (net (code "9") (name "/LPDDR4_A4_A") (class "Default")
      (node (ref "U3000") (pin "H11") (pinfunction "CA4_a_H11") (pintype "passive"))
    )
    (net (code "10") (name "/LPDDR4_A4_B") (class "Default")
      (node (ref "U3000") (pin "R11") (pinfunction "CA4_b_R11") (pintype "passive"))
    )
    (net (code "11") (name "/LPDDR4_A5_A") (class "Default")
      (node (ref "U3000") (pin "J11") (pinfunction "CA5_a_J11") (pintype "passive"))
    )
    (net (code "12") (name "/LPDDR4_A5_B") (class "Default")
      (node (ref "U3000") (pin "P11") (pinfunction "CA5_B_P11") (pintype "passive"))
    )
    (net (code "13") (name "/LPDDR4_CKE0_A") (class "Default")
      (node (ref "U3000") (pin "J4") (pinfunction "CKE0_a_J4") (pintype "passive"))
    )
    (net (code "14") (name "/LPDDR4_CKE0_B") (class "Default")
      (node (ref "U3000") (pin "P4") (pinfunction "CKE0_b_P4") (pintype "passive"))
    )
    (net (code "15") (name "/LPDDR4_CKE1_A") (class "Default")
      (node (ref "U3000") (pin "J5") (pinfunction "CKE1_a_J5") (pintype "passive"))
    )
    (net (code "16") (name "/LPDDR4_CKE1_B") (class "Default")
      (node (ref "U3000") (pin "P5") (pinfunction "CKE1_b_P5") (pintype "passive"))
    )
    (net (code "17") (name "/LPDDR4_CLKN_A") (class "Default")
      (node (ref "U3000") (pin "J9") (pinfunction "CK_c_a_J9") (pintype "passive"))
    )
    (net (code "18") (name "/LPDDR4_CLKN_B") (class "Default")
      (node (ref "U3000") (pin "P9") (pinfunction "CK_c_b_P9") (pintype "passive"))
    )
    (net (code "19") (name "/LPDDR4_CLKP_A") (class "Default")
      (node (ref "U3000") (pin "J8") (pinfunction "CK_t_a_J8") (pintype "passive"))
    )
    (net (code "20") (name "/LPDDR4_CLKP_B") (class "Default")
      (node (ref "U3000") (pin "P8") (pinfunction "CK_t_b_P8") (pintype "passive"))
    )
    (net (code "21") (name "/LPDDR4_CS0n_A") (class "Default")
      (node (ref "U3000") (pin "H4") (pinfunction "CS0_a_H4") (pintype "passive"))
    )
    (net (code "22") (name "/LPDDR4_CS0n_B") (class "Default")
      (node (ref "U3000") (pin "R4") (pinfunction "CS0_b_R4") (pintype "passive"))
    )
    (net (code "23") (name "/LPDDR4_CS1n_A") (class "Default")
      (node (ref "U3000") (pin "H3") (pinfunction "CS1_a_H3") (pintype "passive"))
    )
    (net (code "24") (name "/LPDDR4_CS1n_B") (class "Default")
      (node (ref "U3000") (pin "R3") (pinfunction "CS1_b_R3") (pintype "passive"))
    )
    (net (code "25") (name "/LPDDR4_DM0_A") (class "Default")
      (node (ref "U3000") (pin "C3") (pinfunction "DMI0_a_C3") (pintype "passive"))
    )
    (net (code "26") (name "/LPDDR4_DM0_B") (class "Default")
      (node (ref "U3000") (pin "Y3") (pinfunction "DMI0_b_Y3") (pintype "passive"))
    )
    (net (code "27") (name "/LPDDR4_DM1_A") (class "Default")
      (node (ref "U3000") (pin "C10") (pinfunction "DMI1_a_C10") (pintype "passive"))
    )
    (net (code "28") (name "/LPDDR4_DM1_B") (class "Default")
      (node (ref "U3000") (pin "Y10") (pinfunction "DMI1_b_Y10") (pintype "passive"))
    )
    (net (code "29") (name "/LPDDR4_DQ0_A") (class "Default")
      (node (ref "U3000") (pin "B2") (pinfunction "DQ0_a_B2") (pintype "passive"))
    )
    (net (code "30") (name "/LPDDR4_DQ0_B") (class "Default")
      (node (ref "U3000") (pin "AA2") (pinfunction "DQ0_b_AA2") (pintype "passive"))
    )
    (net (code "31") (name "/LPDDR4_DQ1_A") (class "Default")
      (node (ref "U3000") (pin "C2") (pinfunction "DQ1_a_C2") (pintype "passive"))
    )
    (net (code "32") (name "/LPDDR4_DQ1_B") (class "Default")
      (node (ref "U3000") (pin "Y2") (pinfunction "DQ1_b_Y2") (pintype "passive"))
    )
    (net (code "33") (name "/LPDDR4_DQ2_A") (class "Default")
      (node (ref "U3000") (pin "E2") (pinfunction "DQ2_a_E2") (pintype "passive"))
    )
    (net (code "34") (name "/LPDDR4_DQ2_B") (class "Default")
      (node (ref "U3000") (pin "V2") (pinfunction "DQ2_b_V2") (pintype "passive"))
    )
    (net (code "35") (name "/LPDDR4_DQ3_A") (class "Default")
      (node (ref "U3000") (pin "F2") (pinfunction "DQ3_a_F2") (pintype "passive"))
    )
    (net (code "36") (name "/LPDDR4_DQ3_B") (class "Default")
      (node (ref "U3000") (pin "U2") (pinfunction "DQ3_b_U2") (pintype "passive"))
    )
    (net (code "37") (name "/LPDDR4_DQ4_A") (class "Default")
      (node (ref "U3000") (pin "F4") (pinfunction "DQ4_a_F4") (pintype "passive"))
    )
    (net (code "38") (name "/LPDDR4_DQ4_B") (class "Default")
      (node (ref "U3000") (pin "U4") (pinfunction "DQ4_b_U4") (pintype "passive"))
    )
    (net (code "39") (name "/LPDDR4_DQ5_A") (class "Default")
      (node (ref "U3000") (pin "E4") (pinfunction "DQ5_a_E4") (pintype "passive"))
    )
    (net (code "40") (name "/LPDDR4_DQ5_B") (class "Default")
      (node (ref "U3000") (pin "V4") (pinfunction "DQ5_b_V4") (pintype "passive"))
    )
    (net (code "41") (name "/LPDDR4_DQ6_A") (class "Default")
      (node (ref "U3000") (pin "C4") (pinfunction "DQ6_a_C4") (pintype "passive"))
    )
    (net (code "42") (name "/LPDDR4_DQ6_B") (class "Default")
      (node (ref "U3000") (pin "Y4") (pinfunction "DQ6_b_Y4") (pintype "passive"))
    )
    (net (code "43") (name "/LPDDR4_DQ7_A") (class "Default")
      (node (ref "U3000") (pin "B4") (pinfunction "DQ7_a_B4") (pintype "passive"))
    )
    (net (code "44") (name "/LPDDR4_DQ7_B") (class "Default")
      (node (ref "U3000") (pin "AA4") (pinfunction "DQ7_b_AA4") (pintype "passive"))
    )
    (net (code "45") (name "/LPDDR4_DQ8_A") (class "Default")
      (node (ref "U3000") (pin "B11") (pinfunction "DQ8_a_B11") (pintype "passive"))
    )
    (net (code "46") (name "/LPDDR4_DQ8_B") (class "Default")
      (node (ref "U3000") (pin "AA11") (pinfunction "DQ8_b_AA11") (pintype "passive"))
    )
    (net (code "47") (name "/LPDDR4_DQ9_A") (class "Default")
      (node (ref "U3000") (pin "C11") (pinfunction "DQ9_a_C11") (pintype "passive"))
    )
    (net (code "48") (name "/LPDDR4_DQ9_B") (class "Default")
      (node (ref "U3000") (pin "Y11") (pinfunction "DQ9_b_Y11") (pintype "passive"))
    )
    (net (code "49") (name "/LPDDR4_DQ10_A") (class "Default")
      (node (ref "U3000") (pin "E11") (pinfunction "DQ10_a_E11") (pintype "passive"))
    )
    (net (code "50") (name "/LPDDR4_DQ10_B") (class "Default")
      (node (ref "U3000") (pin "V11") (pinfunction "DQ10_b_V11") (pintype "passive"))
    )
    (net (code "51") (name "/LPDDR4_DQ11_A") (class "Default")
      (node (ref "U3000") (pin "F11") (pinfunction "DQ11_a_F11") (pintype "passive"))
    )
    (net (code "52") (name "/LPDDR4_DQ11_B") (class "Default")
      (node (ref "U3000") (pin "U11") (pinfunction "DQ11_b_U11") (pintype "passive"))
    )
    (net (code "53") (name "/LPDDR4_DQ12_A") (class "Default")
      (node (ref "U3000") (pin "F9") (pinfunction "DQ12_a_F9") (pintype "passive"))
    )
    (net (code "54") (name "/LPDDR4_DQ12_B") (class "Default")
      (node (ref "U3000") (pin "U9") (pinfunction "DQ12_b_U9") (pintype "passive"))
    )
    (net (code "55") (name "/LPDDR4_DQ13_A") (class "Default")
      (node (ref "U3000") (pin "E9") (pinfunction "DQ13_a_E9") (pintype "passive"))
    )
    (net (code "56") (name "/LPDDR4_DQ13_B") (class "Default")
      (node (ref "U3000") (pin "V9") (pinfunction "DQ13_b_V9") (pintype "passive"))
    )
    (net (code "57") (name "/LPDDR4_DQ14_A") (class "Default")
      (node (ref "U3000") (pin "C9") (pinfunction "DQ14_a_C9") (pintype "passive"))
    )
    (net (code "58") (name "/LPDDR4_DQ14_B") (class "Default")
      (node (ref "U3000") (pin "Y9") (pinfunction "DQ14_b_Y9") (pintype "passive"))
    )
    (net (code "59") (name "/LPDDR4_DQ15_A") (class "Default")
      (node (ref "U3000") (pin "B9") (pinfunction "DQ15_a_B9") (pintype "passive"))
    )
    (net (code "60") (name "/LPDDR4_DQ15_B") (class "Default")
      (node (ref "U3000") (pin "AA9") (pinfunction "DQ15_b_AA9") (pintype "passive"))
    )
    (net (code "61") (name "/LPDDR4_DQS0N_A") (class "Default")
      (node (ref "U3000") (pin "E3") (pinfunction "DQS0_c_a_E3") (pintype "passive"))
    )
    (net (code "62") (name "/LPDDR4_DQS0N_B") (class "Default")
      (node (ref "U3000") (pin "V3") (pinfunction "DQS0_c_b_V3") (pintype "passive"))
    )
    (net (code "63") (name "/LPDDR4_DQS0P_A") (class "Default")
      (node (ref "U3000") (pin "D3") (pinfunction "DQS0_t_a_D3") (pintype "passive"))
    )
    (net (code "64") (name "/LPDDR4_DQS0P_B") (class "Default")
      (node (ref "U3000") (pin "W3") (pinfunction "DQS0_t_b_W3") (pintype "passive"))
    )
    (net (code "65") (name "/LPDDR4_DQS1N_A") (class "Default")
      (node (ref "U3000") (pin "E10") (pinfunction "DQS1_c_a_E10") (pintype "passive"))
    )
    (net (code "66") (name "/LPDDR4_DQS1N_B") (class "Default")
      (node (ref "U3000") (pin "V10") (pinfunction "DQS1_c_b_V10") (pintype "passive"))
    )
    (net (code "67") (name "/LPDDR4_DQS1P_A") (class "Default")
      (node (ref "U3000") (pin "D10") (pinfunction "DQS1_t_a_D10") (pintype "passive"))
    )
    (net (code "68") (name "/LPDDR4_DQS1P_B") (class "Default")
      (node (ref "U3000") (pin "W10") (pinfunction "DQS1_t_b_W10") (pintype "passive"))
    )
    (net (code "69") (name "/LPDDR4_RESETn") (class "Default")
      (node (ref "C3001") (pin "1") (pinfunction "1_1") (pintype "passive"))
      (node (ref "U3000") (pin "T11") (pinfunction "RESET_n_T11") (pintype "passive"))
    )
    (net (code "70") (name "GND") (class "Default")
      (node (ref "C3001") (pin "2") (pinfunction "2_2") (pintype "passive"))
      (node (ref "C3002") (pin "2") (pinfunction "2_2") (pintype "passive"))
      (node (ref "C3003") (pin "2") (pinfunction "2_2") (pintype "passive"))
      (node (ref "C3004") (pin "2") (pinfunction "2_2") (pintype "passive"))
      (node (ref "C3005") (pin "2") (pinfunction "2_2") (pintype "passive"))
      (node (ref "C3006") (pin "2") (pinfunction "2_2") (pintype "passive"))
      (node (ref "C3007") (pin "2") (pinfunction "2_2") (pintype "passive"))
      (node (ref "C3008") (pin "2") (pinfunction "2_2") (pintype "passive"))
      (node (ref "C3009") (pin "2") (pinfunction "2_2") (pintype "passive"))
      (node (ref "C3010") (pin "2") (pinfunction "2_2") (pintype "passive"))
      (node (ref "C3011") (pin "2") (pinfunction "2_2") (pintype "passive"))
      (node (ref "C3012") (pin "2") (pinfunction "2_2") (pintype "passive"))
      (node (ref "C3013") (pin "2") (pinfunction "2_2") (pintype "passive"))
      (node (ref "C3014") (pin "2") (pinfunction "2_2") (pintype "passive"))
      (node (ref "C3015") (pin "2") (pinfunction "2_2") (pintype "passive"))
      (node (ref "C3016") (pin "2") (pinfunction "2_2") (pintype "passive"))
      (node (ref "C3017") (pin "2") (pinfunction "2_2") (pintype "passive"))
      (node (ref "C3018") (pin "2") (pinfunction "2_2") (pintype "passive"))
      (node (ref "C3019") (pin "2") (pinfunction "2_2") (pintype "passive"))
      (node (ref "C3020") (pin "2") (pinfunction "2_2") (pintype "passive"))
      (node (ref "C3021") (pin "2") (pinfunction "2_2") (pintype "passive"))
      (node (ref "C3022") (pin "2") (pinfunction "2_2") (pintype "passive"))
      (node (ref "C3023") (pin "2") (pinfunction "2_2") (pintype "passive"))
      (node (ref "C3024") (pin "2") (pinfunction "2_2") (pintype "passive"))
      (node (ref "C3025") (pin "2") (pinfunction "2_2") (pintype "passive"))
      (node (ref "C3026") (pin "2") (pinfunction "2_2") (pintype "passive"))
      (node (ref "C3027") (pin "2") (pinfunction "2_2") (pintype "passive"))
      (node (ref "C3029") (pin "2") (pinfunction "2_2") (pintype "passive"))
      (node (ref "C3030") (pin "2") (pinfunction "2_2") (pintype "passive"))
      (node (ref "C3031") (pin "2") (pinfunction "2_2") (pintype "passive"))
      (node (ref "C3032") (pin "2") (pinfunction "2_2") (pintype "passive"))
      (node (ref "C3033") (pin "2") (pinfunction "2_2") (pintype "passive"))
      (node (ref "C3034") (pin "2") (pinfunction "2_2") (pintype "passive"))
      (node (ref "C3035") (pin "2") (pinfunction "2_2") (pintype "passive"))
      (node (ref "C3036") (pin "2") (pinfunction "2_2") (pintype "passive"))
      (node (ref "C3037") (pin "2") (pinfunction "2_2") (pintype "passive"))
      (node (ref "C3038") (pin "2") (pinfunction "2_2") (pintype "passive"))
      (node (ref "C3039") (pin "2") (pinfunction "2_2") (pintype "passive"))
      (node (ref "C3040") (pin "2") (pinfunction "2_2") (pintype "passive"))
      (node (ref "C3041") (pin "2") (pinfunction "2_2") (pintype "passive"))
      (node (ref "C3042") (pin "2") (pinfunction "2_2") (pintype "passive"))
      (node (ref "C3043") (pin "2") (pinfunction "2_2") (pintype "passive"))
      (node (ref "C3044") (pin "2") (pinfunction "2_2") (pintype "passive"))
      (node (ref "C3045") (pin "2") (pinfunction "2_2") (pintype "passive"))
      (node (ref "C3046") (pin "2") (pinfunction "2_2") (pintype "passive"))
      (node (ref "C3047") (pin "2") (pinfunction "2_2") (pintype "passive"))
      (node (ref "C3048") (pin "2") (pinfunction "2_2") (pintype "passive"))
      (node (ref "C3049") (pin "2") (pinfunction "2_2") (pintype "passive"))
      (node (ref "C3050") (pin "2") (pinfunction "2_2") (pintype "passive"))
      (node (ref "C3051") (pin "2") (pinfunction "2_2") (pintype "passive"))
      (node (ref "C3052") (pin "2") (pinfunction "2_2") (pintype "passive"))
      (node (ref "C3055") (pin "2") (pinfunction "2_2") (pintype "passive"))
      (node (ref "C3060") (pin "2") (pinfunction "2_2") (pintype "passive"))
      (node (ref "C3062") (pin "2") (pinfunction "2_2") (pintype "passive"))
      (node (ref "C3064") (pin "2") (pinfunction "2_2") (pintype "passive"))
      (node (ref "C3066") (pin "2") (pinfunction "2_2") (pintype "passive"))
      (node (ref "R3012") (pin "2") (pinfunction "2_2") (pintype "passive"))
      (node (ref "U3000") (pin "A10") (pinfunction "VSS_2_A10") (pintype "power_in"))
      (node (ref "U3000") (pin "A3") (pinfunction "VSS_1_A3") (pintype "power_in"))
      (node (ref "U3000") (pin "AB10") (pinfunction "VSS_58_AB10") (pintype "power_in"))
      (node (ref "U3000") (pin "AB3") (pinfunction "VSS_55_AB3") (pintype "power_in"))
      (node (ref "U3000") (pin "AB5") (pinfunction "VSS_56_AB5") (pintype "power_in"))
      (node (ref "U3000") (pin "AB8") (pinfunction "VSS_57_AB8") (pintype "power_in"))
      (node (ref "U3000") (pin "C1") (pinfunction "VSS_3_C1") (pintype "power_in"))
      (node (ref "U3000") (pin "C12") (pinfunction "VSS_6_C12") (pintype "power_in"))
      (node (ref "U3000") (pin "C5") (pinfunction "VSS_4_C5") (pintype "power_in"))
      (node (ref "U3000") (pin "C8") (pinfunction "VSS_5_C8") (pintype "power_in"))
      (node (ref "U3000") (pin "D11") (pinfunction "VSS_10_D11") (pintype "power_in"))
      (node (ref "U3000") (pin "D2") (pinfunction "VSS_7_D2") (pintype "power_in"))
      (node (ref "U3000") (pin "D4") (pinfunction "VSS_8_D4") (pintype "power_in"))
      (node (ref "U3000") (pin "D9") (pinfunction "VSS_9_D9") (pintype "power_in"))
      (node (ref "U3000") (pin "E1") (pinfunction "VSS_11_E1") (pintype "power_in"))
      (node (ref "U3000") (pin "E12") (pinfunction "VSS_14_E12") (pintype "power_in"))
      (node (ref "U3000") (pin "E5") (pinfunction "VSS_12_E5") (pintype "power_in"))
      (node (ref "U3000") (pin "E8") (pinfunction "VSS_13_E8") (pintype "power_in"))
      (node (ref "U3000") (pin "G1") (pinfunction "VSS_15_G1") (pintype "power_in"))
      (node (ref "U3000") (pin "G10") (pinfunction "VSS_19_G10") (pintype "power_in"))
      (node (ref "U3000") (pin "G12") (pinfunction "VSS_20_G12") (pintype "power_in"))
      (node (ref "U3000") (pin "G3") (pinfunction "VSS_16_G3") (pintype "power_in"))
      (node (ref "U3000") (pin "G5") (pinfunction "VSS_17_G5") (pintype "power_in"))
      (node (ref "U3000") (pin "G8") (pinfunction "VSS_18_G8") (pintype "power_in"))
      (node (ref "U3000") (pin "J1") (pinfunction "VSS_21_J1") (pintype "power_in"))
      (node (ref "U3000") (pin "J10") (pinfunction "VSS_23_J10") (pintype "power_in"))
      (node (ref "U3000") (pin "J12") (pinfunction "VSS_24_J12") (pintype "power_in"))
      (node (ref "U3000") (pin "J3") (pinfunction "VSS_22_J3") (pintype "power_in"))
      (node (ref "U3000") (pin "K11") (pinfunction "VSS_28_K11") (pintype "power_in"))
      (node (ref "U3000") (pin "K2") (pinfunction "VSS_25_K2") (pintype "power_in"))
      (node (ref "U3000") (pin "K4") (pinfunction "VSS_26_K4") (pintype "power_in"))
      (node (ref "U3000") (pin "K9") (pinfunction "VSS_27_K9") (pintype "power_in"))
      (node (ref "U3000") (pin "N11") (pinfunction "VSS_32_N11") (pintype "power_in"))
      (node (ref "U3000") (pin "N2") (pinfunction "VSS_29_N2") (pintype "power_in"))
      (node (ref "U3000") (pin "N4") (pinfunction "VSS_30_N4") (pintype "power_in"))
      (node (ref "U3000") (pin "N9") (pinfunction "VSS_31_N9") (pintype "power_in"))
      (node (ref "U3000") (pin "P1") (pinfunction "VSS_33_P1") (pintype "power_in"))
      (node (ref "U3000") (pin "P10") (pinfunction "VSS_35_P10") (pintype "power_in"))
      (node (ref "U3000") (pin "P12") (pinfunction "VSS_36_P12") (pintype "power_in"))
      (node (ref "U3000") (pin "P3") (pinfunction "VSS_34_P3") (pintype "power_in"))
      (node (ref "U3000") (pin "T1") (pinfunction "VSS_37_T1") (pintype "power_in"))
      (node (ref "U3000") (pin "T10") (pinfunction "VSS_41_T10") (pintype "power_in"))
      (node (ref "U3000") (pin "T12") (pinfunction "VSS_42_T12") (pintype "power_in"))
      (node (ref "U3000") (pin "T3") (pinfunction "VSS_38_T3") (pintype "power_in"))
      (node (ref "U3000") (pin "T5") (pinfunction "VSS_39_T5") (pintype "power_in"))
      (node (ref "U3000") (pin "T8") (pinfunction "VSS_40_T8") (pintype "power_in"))
      (node (ref "U3000") (pin "V1") (pinfunction "VSS_43_V1") (pintype "power_in"))
      (node (ref "U3000") (pin "V12") (pinfunction "VSS_46_V12") (pintype "power_in"))
      (node (ref "U3000") (pin "V5") (pinfunction "VSS_44_V5") (pintype "power_in"))
      (node (ref "U3000") (pin "V8") (pinfunction "VSS_45_V8") (pintype "power_in"))
      (node (ref "U3000") (pin "W11") (pinfunction "VSS_50_W11") (pintype "power_in"))
      (node (ref "U3000") (pin "W2") (pinfunction "VSS_47_W2") (pintype "power_in"))
      (node (ref "U3000") (pin "W4") (pinfunction "VSS_48_W4") (pintype "power_in"))
      (node (ref "U3000") (pin "W9") (pinfunction "VSS_49_W9") (pintype "power_in"))
      (node (ref "U3000") (pin "Y1") (pinfunction "VSS_51_Y1") (pintype "power_in"))
      (node (ref "U3000") (pin "Y12") (pinfunction "VSS_54_Y12") (pintype "power_in"))
      (node (ref "U3000") (pin "Y5") (pinfunction "VSS_52_Y5") (pintype "power_in"))
      (node (ref "U3000") (pin "Y8") (pinfunction "VSS_53_Y8") (pintype "power_in"))
      (node (ref "U3002") (pin "2") (pinfunction "GND_2") (pintype "passive"))
    )
    (net (code "71") (name "Net-(U3000A-ZQ0)") (class "Default")
      (node (ref "R3002") (pin "2") (pinfunction "2_2") (pintype "passive"))
      (node (ref "U3000") (pin "A5") (pinfunction "ZQ0_A5") (pintype "passive"))
    )
    (net (code "72") (name "Net-(U3000A-ZQ1)") (class "Default")
      (node (ref "R3001") (pin "2") (pinfunction "2_2") (pintype "passive"))
      (node (ref "U3000") (pin "A8") (pinfunction "ZQ1_A8") (pintype "passive"))
    )
    (net (code "73") (name "Net-(U3002-EN)") (class "Default")
      (node (ref "C3066") (pin "1") (pinfunction "1_1") (pintype "passive"))
      (node (ref "R3010") (pin "2") (pinfunction "2_2") (pintype "passive"))
      (node (ref "U3002") (pin "1") (pinfunction "EN_1") (pintype "passive"))
    )
    (net (code "74") (name "Net-(U3002-FB{slash}OUT)") (class "Default")
      (node (ref "C3061") (pin "2") (pinfunction "2_2") (pintype "passive"))
      (node (ref "R3011") (pin "2") (pinfunction "2_2") (pintype "passive"))
      (node (ref "R3012") (pin "1") (pinfunction "1_1") (pintype "passive"))
      (node (ref "U3002") (pin "5") (pinfunction "FB/OUT_5") (pintype "passive"))
    )
    (net (code "75") (name "Net-(U3002-LX)") (class "Default")
      (node (ref "L3001") (pin "1") (pinfunction "1_1") (pintype "passive"))
      (node (ref "U3002") (pin "3") (pinfunction "LX_3") (pintype "passive"))
    )
    (net (code "76") (name "VCC0V6_DDR") (class "Default")
      (node (ref "C3029") (pin "1") (pinfunction "1_1") (pintype "passive"))
      (node (ref "C3030") (pin "1") (pinfunction "1_1") (pintype "passive"))
      (node (ref "C3031") (pin "1") (pinfunction "1_1") (pintype "passive"))
      (node (ref "C3032") (pin "1") (pinfunction "1_1") (pintype "passive"))
      (node (ref "C3033") (pin "1") (pinfunction "1_1") (pintype "passive"))
      (node (ref "C3034") (pin "1") (pinfunction "1_1") (pintype "passive"))
      (node (ref "C3035") (pin "1") (pinfunction "1_1") (pintype "passive"))
      (node (ref "C3036") (pin "1") (pinfunction "1_1") (pintype "passive"))
      (node (ref "C3037") (pin "1") (pinfunction "1_1") (pintype "passive"))
      (node (ref "C3038") (pin "1") (pinfunction "1_1") (pintype "passive"))
      (node (ref "C3039") (pin "1") (pinfunction "1_1") (pintype "passive"))
      (node (ref "C3040") (pin "1") (pinfunction "1_1") (pintype "passive"))
      (node (ref "C3041") (pin "1") (pinfunction "1_1") (pintype "passive"))
      (node (ref "C3042") (pin "1") (pinfunction "1_1") (pintype "passive"))
      (node (ref "C3043") (pin "1") (pinfunction "1_1") (pintype "passive"))
      (node (ref "C3044") (pin "1") (pinfunction "1_1") (pintype "passive"))
      (node (ref "C3045") (pin "1") (pinfunction "1_1") (pintype "passive"))
      (node (ref "C3046") (pin "1") (pinfunction "1_1") (pintype "passive"))
      (node (ref "C3047") (pin "1") (pinfunction "1_1") (pintype "passive"))
      (node (ref "C3048") (pin "1") (pinfunction "1_1") (pintype "passive"))
      (node (ref "C3064") (pin "1") (pinfunction "1_1") (pintype "passive"))
      (node (ref "R3001") (pin "1") (pinfunction "1_1") (pintype "passive"))
      (node (ref "R3002") (pin "1") (pinfunction "1_1") (pintype "passive"))
      (node (ref "R3011") (pin "1") (pinfunction "1_1") (pintype "passive"))
      (node (ref "R3013") (pin "2") (pinfunction "2_2") (pintype "passive"))
      (node (ref "R3014") (pin "2") (pinfunction "2_2") (pintype "passive"))
      (node (ref "U3000") (pin "AA10") (pinfunction "VDDQ_20_AA10") (pintype "power_in"))
      (node (ref "U3000") (pin "AA3") (pinfunction "VDDQ_17_AA3") (pintype "power_in"))
      (node (ref "U3000") (pin "AA5") (pinfunction "VDDQ_18_AA5") (pintype "power_in"))
      (node (ref "U3000") (pin "AA8") (pinfunction "VDDQ_19_AA8") (pintype "power_in"))
      (node (ref "U3000") (pin "B10") (pinfunction "VDDQ_4_B10") (pintype "power_in"))
      (node (ref "U3000") (pin "B3") (pinfunction "VDDQ_1_B3") (pintype "power_in"))
      (node (ref "U3000") (pin "B5") (pinfunction "VDDQ_2_B5") (pintype "power_in"))
      (node (ref "U3000") (pin "B8") (pinfunction "VDDQ_3_B8") (pintype "power_in"))
      (node (ref "U3000") (pin "D1") (pinfunction "VDDQ_5_D1") (pintype "power_in"))
      (node (ref "U3000") (pin "D12") (pinfunction "VDDQ_8_D12") (pintype "power_in"))
      (node (ref "U3000") (pin "D5") (pinfunction "VDDQ_6_D5") (pintype "power_in"))
      (node (ref "U3000") (pin "D8") (pinfunction "VDDQ_7_D8") (pintype "power_in"))
      (node (ref "U3000") (pin "F10") (pinfunction "VDDQ_10_F10") (pintype "power_in"))
      (node (ref "U3000") (pin "F3") (pinfunction "VDDQ_9_F3") (pintype "power_in"))
      (node (ref "U3000") (pin "U10") (pinfunction "VDDQ_12_U10") (pintype "power_in"))
      (node (ref "U3000") (pin "U3") (pinfunction "VDDQ_11_U3") (pintype "power_in"))
      (node (ref "U3000") (pin "W1") (pinfunction "VDDQ_13_W1") (pintype "power_in"))
      (node (ref "U3000") (pin "W12") (pinfunction "VDDQ_16_W12") (pintype "power_in"))
      (node (ref "U3000") (pin "W5") (pinfunction "VDDQ_14_W5") (pintype "power_in"))
      (node (ref "U3000") (pin "W8") (pinfunction "VDDQ_15_W8") (pintype "power_in"))
    )
    (net (code "77") (name "VCC0V6_DDR_P") (class "Default")
      (node (ref "C3061") (pin "1") (pinfunction "1_1") (pintype "passive"))
      (node (ref "C3062") (pin "1") (pinfunction "1_1") (pintype "passive"))
      (node (ref "L3001") (pin "2") (pinfunction "2_2") (pintype "passive"))
      (node (ref "R3014") (pin "1") (pinfunction "1_1") (pintype "passive"))
    )
    (net (code "78") (name "VCC1V8_DDR") (class "Default")
      (node (ref "C3024") (pin "1") (pinfunction "1_1") (pintype "passive"))
      (node (ref "C3025") (pin "1") (pinfunction "1_1") (pintype "passive"))
      (node (ref "C3026") (pin "1") (pinfunction "1_1") (pintype "passive"))
      (node (ref "C3027") (pin "1") (pinfunction "1_1") (pintype "passive"))
      (node (ref "C3049") (pin "1") (pinfunction "1_1") (pintype "passive"))
      (node (ref "C3050") (pin "1") (pinfunction "1_1") (pintype "passive"))
      (node (ref "C3051") (pin "1") (pinfunction "1_1") (pintype "passive"))
      (node (ref "C3052") (pin "1") (pinfunction "1_1") (pintype "passive"))
      (node (ref "R3010") (pin "1") (pinfunction "1_1") (pintype "passive"))
      (node (ref "R3015") (pin "2") (pinfunction "2_2") (pintype "passive"))
      (node (ref "U3000") (pin "F1") (pinfunction "VDD1_1_F1") (pintype "power_in"))
      (node (ref "U3000") (pin "F12") (pinfunction "VDD1_2_F12") (pintype "power_in"))
      (node (ref "U3000") (pin "G4") (pinfunction "VDD1_3_G4") (pintype "power_in"))
      (node (ref "U3000") (pin "G9") (pinfunction "VDD1_4_G9") (pintype "power_in"))
      (node (ref "U3000") (pin "T4") (pinfunction "VDD1_5_T4") (pintype "power_in"))
      (node (ref "U3000") (pin "T9") (pinfunction "VDD1_6_T9") (pintype "power_in"))
      (node (ref "U3000") (pin "U1") (pinfunction "VDD1_7_U1") (pintype "power_in"))
      (node (ref "U3000") (pin "U12") (pinfunction "VDD1_8_U12") (pintype "power_in"))
    )
    (net (code "79") (name "VCC3V3_SYS") (class "Default")
      (node (ref "C3060") (pin "1") (pinfunction "1_1") (pintype "passive"))
      (node (ref "U3002") (pin "4") (pinfunction "VIN_4") (pintype "passive"))
    )
    (net (code "80") (name "VCCA1V8_PMU") (class "Default")
      (node (ref "C3055") (pin "1") (pinfunction "1_1") (pintype "passive"))
      (node (ref "R3015") (pin "1") (pinfunction "1_1") (pintype "passive"))
    )
    (net (code "81") (name "VCC_DDR") (class "Default")
      (node (ref "C3002") (pin "1") (pinfunction "1_1") (pintype "passive"))
      (node (ref "C3003") (pin "1") (pinfunction "1_1") (pintype "passive"))
      (node (ref "C3004") (pin "1") (pinfunction "1_1") (pintype "passive"))
      (node (ref "C3005") (pin "1") (pinfunction "1_1") (pintype "passive"))
      (node (ref "C3006") (pin "1") (pinfunction "1_1") (pintype "passive"))
      (node (ref "C3007") (pin "1") (pinfunction "1_1") (pintype "passive"))
      (node (ref "C3008") (pin "1") (pinfunction "1_1") (pintype "passive"))
      (node (ref "C3009") (pin "1") (pinfunction "1_1") (pintype "passive"))
      (node (ref "C3010") (pin "1") (pinfunction "1_1") (pintype "passive"))
      (node (ref "C3011") (pin "1") (pinfunction "1_1") (pintype "passive"))
      (node (ref "C3012") (pin "1") (pinfunction "1_1") (pintype "passive"))
      (node (ref "C3013") (pin "1") (pinfunction "1_1") (pintype "passive"))
      (node (ref "C3014") (pin "1") (pinfunction "1_1") (pintype "passive"))
      (node (ref "C3015") (pin "1") (pinfunction "1_1") (pintype "passive"))
      (node (ref "C3016") (pin "1") (pinfunction "1_1") (pintype "passive"))
      (node (ref "C3017") (pin "1") (pinfunction "1_1") (pintype "passive"))
      (node (ref "C3018") (pin "1") (pinfunction "1_1") (pintype "passive"))
      (node (ref "C3019") (pin "1") (pinfunction "1_1") (pintype "passive"))
      (node (ref "C3020") (pin "1") (pinfunction "1_1") (pintype "passive"))
      (node (ref "C3021") (pin "1") (pinfunction "1_1") (pintype "passive"))
      (node (ref "C3022") (pin "1") (pinfunction "1_1") (pintype "passive"))
      (node (ref "C3023") (pin "1") (pinfunction "1_1") (pintype "passive"))
      (node (ref "R3013") (pin "1") (pinfunction "1_1") (pintype "passive"))
      (node (ref "U3000") (pin "A4") (pinfunction "VDD2_1_A4") (pintype "power_in"))
      (node (ref "U3000") (pin "A9") (pinfunction "VDD2_2_A9") (pintype "power_in"))
      (node (ref "U3000") (pin "AB4") (pinfunction "VDD2_23_AB4") (pintype "power_in"))
      (node (ref "U3000") (pin "AB9") (pinfunction "VDD2_24_AB9") (pintype "power_in"))
      (node (ref "U3000") (pin "F5") (pinfunction "VDD2_3_F5") (pintype "power_in"))
      (node (ref "U3000") (pin "F8") (pinfunction "VDD2_4_F8") (pintype "power_in"))
      (node (ref "U3000") (pin "G2") (pinfunction "ODT_CA_a_G2") (pintype "passive"))
      (node (ref "U3000") (pin "H1") (pinfunction "VDD2_5_H1") (pintype "power_in"))
      (node (ref "U3000") (pin "H12") (pinfunction "VDD2_8_H12") (pintype "power_in"))
      (node (ref "U3000") (pin "H5") (pinfunction "VDD2_6_H5") (pintype "power_in"))
      (node (ref "U3000") (pin "H8") (pinfunction "VDD2_7_H8") (pintype "power_in"))
      (node (ref "U3000") (pin "K1") (pinfunction "VDD2_9_K1") (pintype "power_in"))
      (node (ref "U3000") (pin "K10") (pinfunction "VDD2_11_K10") (pintype "power_in"))
      (node (ref "U3000") (pin "K12") (pinfunction "VDD2_12_K12") (pintype "power_in"))
      (node (ref "U3000") (pin "K3") (pinfunction "VDD2_10_K3") (pintype "power_in"))
      (node (ref "U3000") (pin "N1") (pinfunction "VDD2_13_N1") (pintype "power_in"))
      (node (ref "U3000") (pin "N10") (pinfunction "VDD2_15_N10") (pintype "power_in"))
      (node (ref "U3000") (pin "N12") (pinfunction "VDD2_16_N12") (pintype "power_in"))
      (node (ref "U3000") (pin "N3") (pinfunction "VDD2_14_N3") (pintype "power_in"))
      (node (ref "U3000") (pin "R1") (pinfunction "VDD2_17_R1") (pintype "power_in"))
      (node (ref "U3000") (pin "R12") (pinfunction "VDD2_20_R12") (pintype "power_in"))
      (node (ref "U3000") (pin "R5") (pinfunction "VDD2_18_R5") (pintype "power_in"))
      (node (ref "U3000") (pin "R8") (pinfunction "VDD2_19_R8") (pintype "power_in"))
      (node (ref "U3000") (pin "T2") (pinfunction "ODT_CA_b_T2") (pintype "passive"))
      (node (ref "U3000") (pin "U5") (pinfunction "VDD2_21_U5") (pintype "power_in"))
      (node (ref "U3000") (pin "U8") (pinfunction "VDD2_22_U8") (pintype "power_in"))
    )
    (net (code "82") (name "unconnected-(U3000A-CKE2_a_NC-PadK8)") (class "Default")
      (node (ref "U3000") (pin "K8") (pinfunction "CKE2_a_NC_K8") (pintype "passive+no_connect"))
    )
    (net (code "83") (name "unconnected-(U3000A-CKE2_b_NC-PadN8)") (class "Default")
      (node (ref "U3000") (pin "N8") (pinfunction "CKE2_b_NC_N8") (pintype "passive+no_connect"))
    )
    (net (code "84") (name "unconnected-(U3000A-CS2_a_NC-PadK5)") (class "Default")
      (node (ref "U3000") (pin "K5") (pinfunction "CS2_a_NC_K5") (pintype "passive+no_connect"))
    )
    (net (code "85") (name "unconnected-(U3000A-CS2_b_NC-PadN5)") (class "Default")
      (node (ref "U3000") (pin "N5") (pinfunction "CS2_b_NC_N5") (pintype "passive+no_connect"))
    )
    (net (code "86") (name "unconnected-(U3000A-ZQ2_NC-PadG11)") (class "Default")
      (node (ref "U3000") (pin "G11") (pinfunction "ZQ2_NC_G11") (pintype "passive+no_connect"))
    )
    (net (code "87") (name "unconnected-(U3000B-DNU_1-PadA1)") (class "Default")
      (node (ref "U3000") (pin "A1") (pinfunction "DNU_1_A1") (pintype "passive+no_connect"))
    )
    (net (code "88") (name "unconnected-(U3000B-DNU_2-PadA2)") (class "Default")
      (node (ref "U3000") (pin "A2") (pinfunction "DNU_2_A2") (pintype "passive+no_connect"))
    )
    (net (code "89") (name "unconnected-(U3000B-DNU_3-PadA11)") (class "Default")
      (node (ref "U3000") (pin "A11") (pinfunction "DNU_3_A11") (pintype "passive+no_connect"))
    )
    (net (code "90") (name "unconnected-(U3000B-DNU_4-PadA12)") (class "Default")
      (node (ref "U3000") (pin "A12") (pinfunction "DNU_4_A12") (pintype "passive+no_connect"))
    )
    (net (code "91") (name "unconnected-(U3000B-DNU_5-PadB1)") (class "Default")
      (node (ref "U3000") (pin "B1") (pinfunction "DNU_5_B1") (pintype "passive+no_connect"))
    )
    (net (code "92") (name "unconnected-(U3000B-DNU_6-PadB12)") (class "Default")
      (node (ref "U3000") (pin "B12") (pinfunction "DNU_6_B12") (pintype "passive+no_connect"))
    )
    (net (code "93") (name "unconnected-(U3000B-DNU_7-PadAA1)") (class "Default")
      (node (ref "U3000") (pin "AA1") (pinfunction "DNU_7_AA1") (pintype "passive+no_connect"))
    )
    (net (code "94") (name "unconnected-(U3000B-DNU_8-PadAA12)") (class "Default")
      (node (ref "U3000") (pin "AA12") (pinfunction "DNU_8_AA12") (pintype "passive+no_connect"))
    )
    (net (code "95") (name "unconnected-(U3000B-DNU_9-PadAB1)") (class "Default")
      (node (ref "U3000") (pin "AB1") (pinfunction "DNU_9_AB1") (pintype "passive+no_connect"))
    )
    (net (code "96") (name "unconnected-(U3000B-DNU_10-PadAB2)") (class "Default")
      (node (ref "U3000") (pin "AB2") (pinfunction "DNU_10_AB2") (pintype "passive+no_connect"))
    )
    (net (code "97") (name "unconnected-(U3000B-DNU_11-PadAB11)") (class "Default")
      (node (ref "U3000") (pin "AB11") (pinfunction "DNU_11_AB11") (pintype "passive+no_connect"))
    )
    (net (code "98") (name "unconnected-(U3000B-DNU_12-PadAB12)") (class "Default")
      (node (ref "U3000") (pin "AB12") (pinfunction "DNU_12_AB12") (pintype "passive+no_connect"))
    )
  )
)
